# uebung1.net
KiCad netlist of a schematic drawn in EAGLE
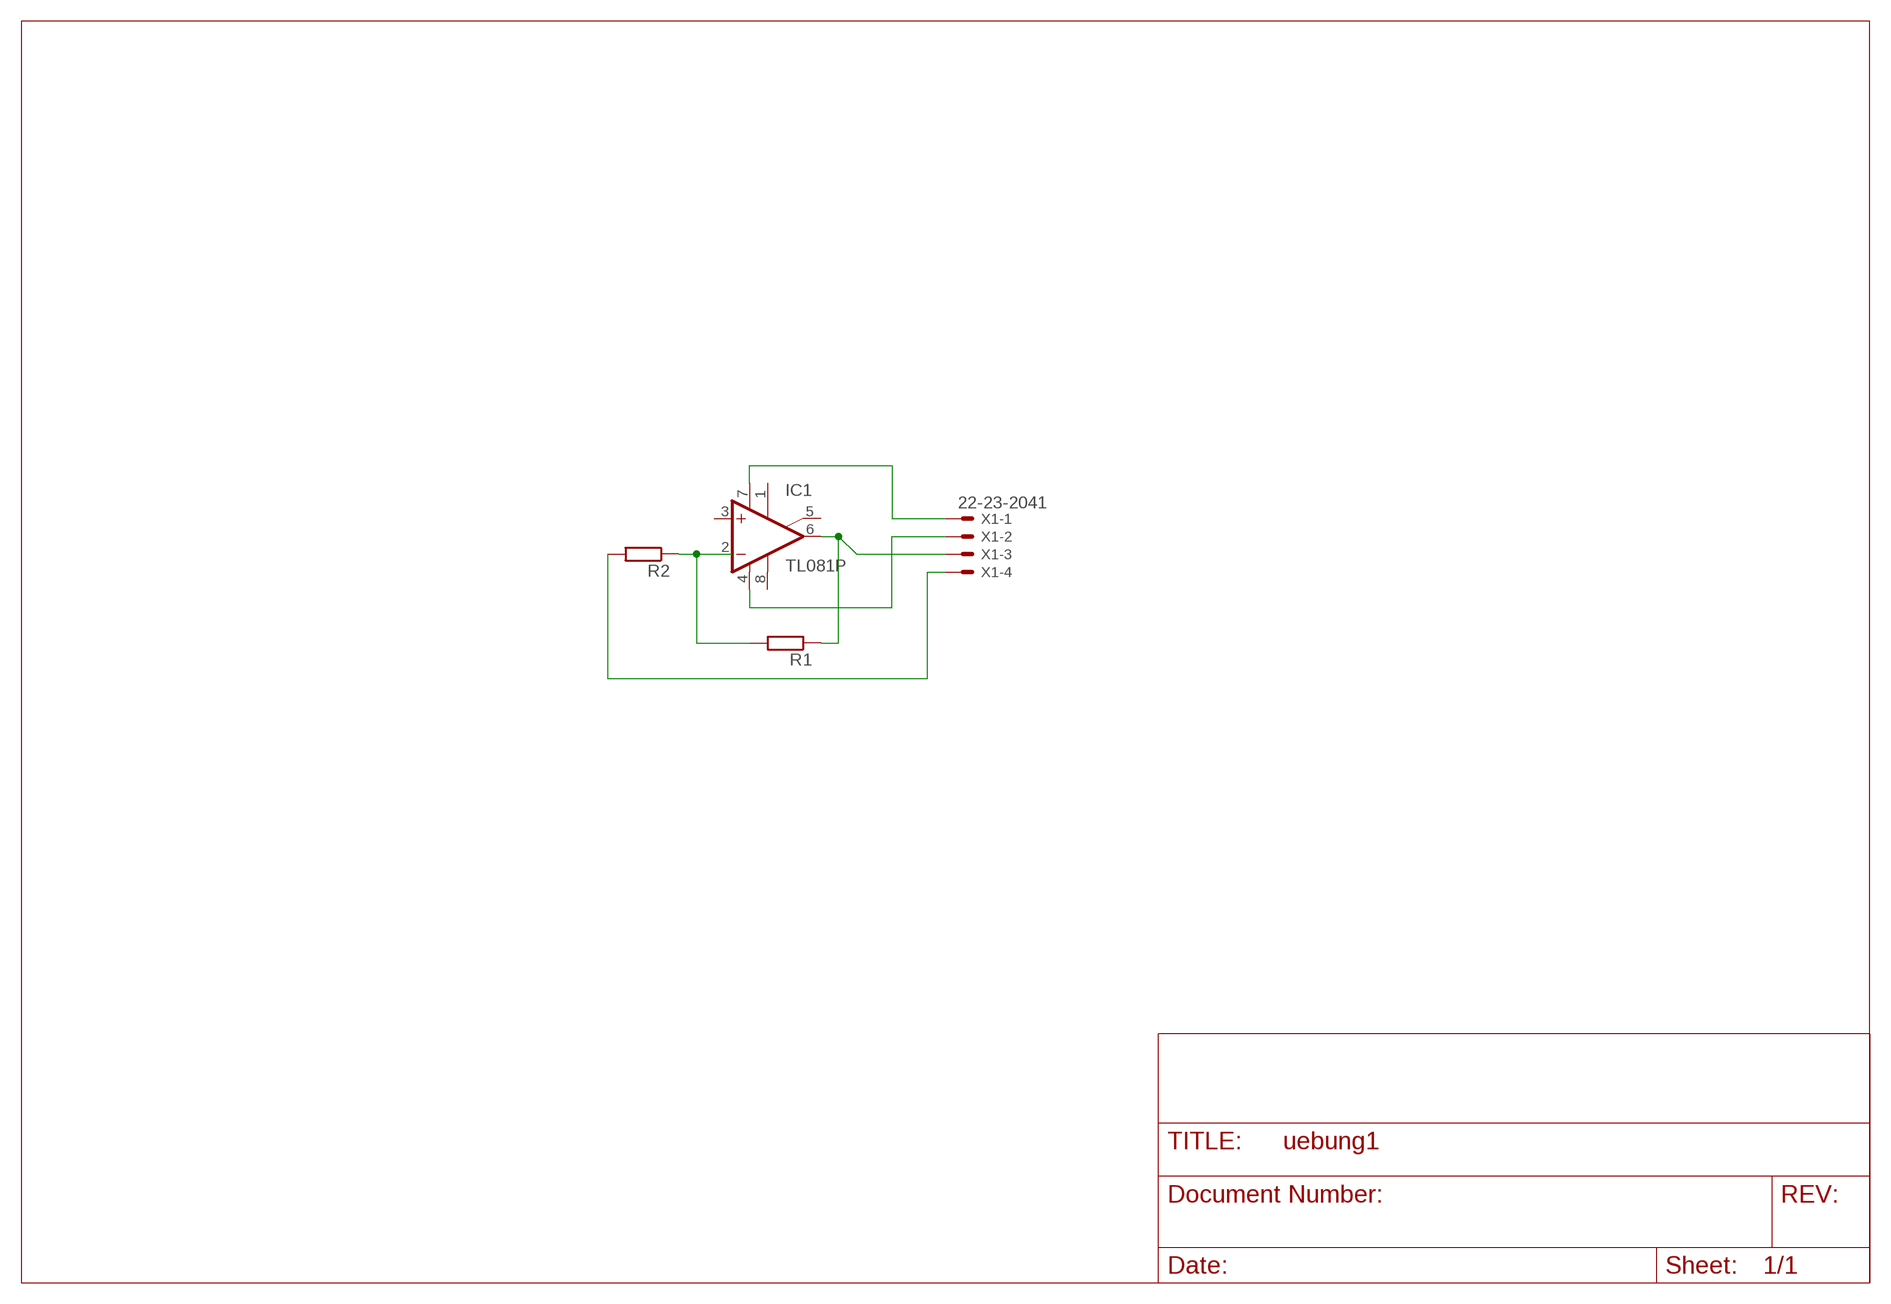
[diagram p0: schematic, sheet 1]

(export (version "E")
  (design (tool "Eeschema 10.0.6"))
  (components
    (comp (ref "IC1")
      (value "TL081P")
      (footprint "eagle-import:DIL08")
      (libsource (lib "eagle-import") (part "TL081P"))
    )
    (comp (ref "R1")
      (value "R-EU_0207/10")
      (footprint "eagle-import:0207_10")
      (libsource (lib "eagle-import") (part "R-EU_0207/10"))
    )
    (comp (ref "R2")
      (value "R-EU_0207/10")
      (footprint "eagle-import:0207_10")
      (libsource (lib "eagle-import") (part "R-EU_0207/10"))
    )
    (comp (ref "X1")
      (value "22-23-2041")
      (footprint "eagle-import:22-23-2041")
      (fields (field (name "MF") "MOLEX"))
      (libsource (lib "eagle-import") (part "22-23-2041"))
    )
  )
  (nets
    (net (code "1") (name "Net-(IC1-OUT)") (class "Default")
      (node (ref "IC1") (pin "6") (pinfunction "OUT_6") (pintype "output"))
      (node (ref "R1") (pin "1") (pinfunction "1_1") (pintype "passive"))
      (node (ref "X1") (pin "3") (pinfunction "S_3") (pintype "passive"))
    )
    (net (code "2") (name "Net-(IC1-V+)") (class "Default")
      (node (ref "IC1") (pin "7") (pinfunction "V+_7") (pintype "power_in"))
      (node (ref "X1") (pin "1") (pinfunction "S_1") (pintype "passive"))
    )
    (net (code "3") (name "Net-(IC1-V-)") (class "Default")
      (node (ref "IC1") (pin "4") (pinfunction "V-_4") (pintype "power_in"))
      (node (ref "X1") (pin "2") (pinfunction "S_2") (pintype "passive"))
    )
    (net (code "4") (name "Net-(R1-Pad2)") (class "Default")
      (node (ref "R1") (pin "2") (pinfunction "2_2") (pintype "passive"))
      (node (ref "R2") (pin "1") (pinfunction "1_1") (pintype "passive"))
    )
    (net (code "5") (name "Net-(X1D-S)") (class "Default")
      (node (ref "R2") (pin "2") (pinfunction "2_2") (pintype "passive"))
      (node (ref "X1") (pin "4") (pinfunction "S_4") (pintype "passive"))
    )
    (net (code "6") (name "unconnected-(IC1-+IN-Pad3)") (class "Default")
      (node (ref "IC1") (pin "3") (pinfunction "+IN_3") (pintype "input"))
    )
    (net (code "7") (name "unconnected-(IC1--IN-Pad2)") (class "Default")
      (node (ref "IC1") (pin "2") (pinfunction "-IN_2") (pintype "input"))
    )
    (net (code "8") (name "unconnected-(IC1-ON1-Pad1)") (class "Default")
      (node (ref "IC1") (pin "1") (pinfunction "ON1_1") (pintype "passive"))
    )
    (net (code "9") (name "unconnected-(IC1-ON2-Pad5)") (class "Default")
      (node (ref "IC1") (pin "5") (pinfunction "ON2_5") (pintype "passive"))
    )
    (net (code "10") (name "unconnected-(IC1-OPT-Pad8)") (class "Default")
      (node (ref "IC1") (pin "8") (pinfunction "OPT_8") (pintype "passive"))
    )
  )
)
